# JHP.net
KiCad netlist of a schematic drawn in EasyEDA Pro
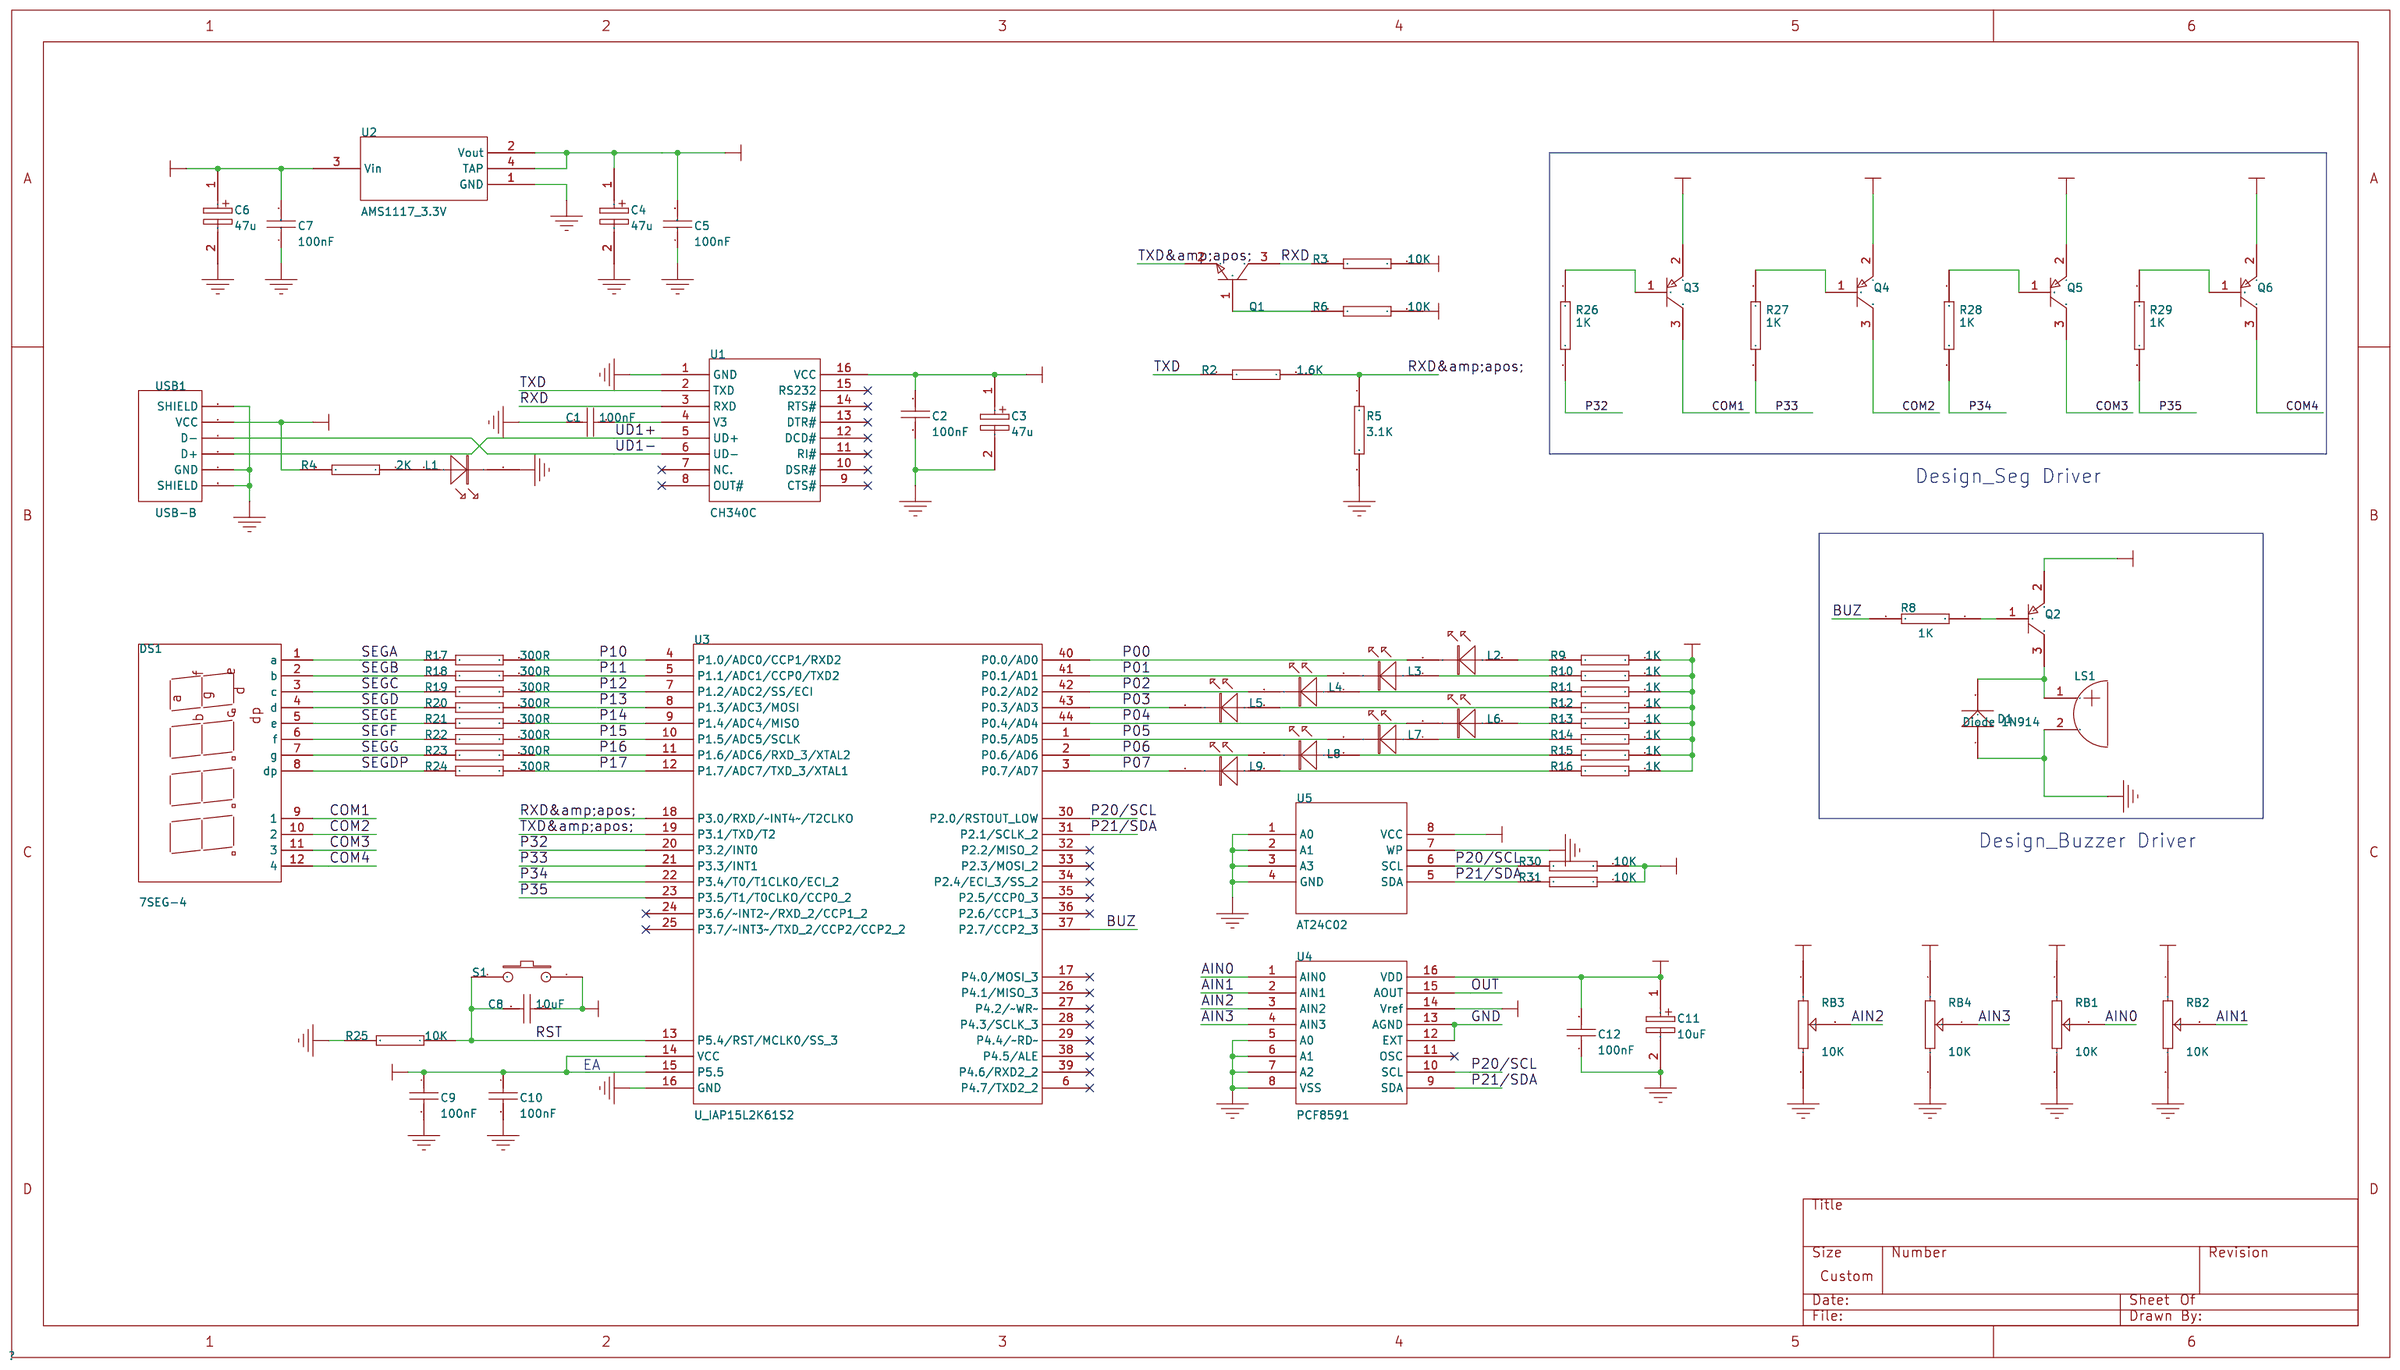
[diagram p0: schematic sheet]

(export (version "E")
  (design (tool "Eeschema 10.0.6"))
  (components
    (comp (ref "C1") (value "100nF") (libsource (lib "easyedapro") (part "CAP")))
    (comp (ref "C2") (value "100nF") (libsource (lib "easyedapro") (part "CAP")))
    (comp (ref "C3")
      (value "47u")
      (description "Electrolytic Capacitor")
      (libsource (lib "easyedapro") (part "CAP-2"))
    )
    (comp (ref "C4")
      (value "47u")
      (description "Electrolytic Capacitor")
      (libsource (lib "easyedapro") (part "CAP-2"))
    )
    (comp (ref "C5") (value "100nF") (description "Capacitor") (libsource (lib "easyedapro") (part "C_CAP")))
    (comp (ref "C6")
      (value "47u")
      (description "Electrolytic Capacitor")
      (libsource (lib "easyedapro") (part "CAP-2"))
    )
    (comp (ref "C7") (value "100nF") (description "Capacitor") (libsource (lib "easyedapro") (part "C_CAP")))
    (comp (ref "C8") (value "10uF") (libsource (lib "easyedapro") (part "CAP")))
    (comp (ref "C9") (value "100nF") (libsource (lib "easyedapro") (part "CAP")))
    (comp (ref "C10") (value "100nF") (libsource (lib "easyedapro") (part "CAP")))
    (comp (ref "C11")
      (value "10uF")
      (description "Electrolytic Capacitor")
      (libsource (lib "easyedapro") (part "ELECTRO2"))
    )
    (comp (ref "C12") (value "100nF") (description "Capacitor") (libsource (lib "easyedapro") (part "CAP")))
    (comp (ref "D1")
      (value "Diode 1N914")
      (description "High Conductance Fast Diode")
      (libsource (lib "easyedapro") (part "Diode 1N914"))
    )
    (comp (ref "DS1")
      (value "7SEG-4")
      (description "4 Seven-Segment Display, Right Hand Decimal")
      (libsource (lib "easyedapro") (part "7SEG-4"))
    )
    (comp (ref "L1") (value "LED") (libsource (lib "easyedapro") (part "LED")))
    (comp (ref "L2") (value "LED") (libsource (lib "easyedapro") (part "LED")))
    (comp (ref "L3") (value "LED") (libsource (lib "easyedapro") (part "LED")))
    (comp (ref "L4") (value "LED") (libsource (lib "easyedapro") (part "LED")))
    (comp (ref "L5") (value "LED") (libsource (lib "easyedapro") (part "LED")))
    (comp (ref "L6") (value "LED") (libsource (lib "easyedapro") (part "LED")))
    (comp (ref "L7") (value "LED") (libsource (lib "easyedapro") (part "LED")))
    (comp (ref "L8") (value "LED") (libsource (lib "easyedapro") (part "LED")))
    (comp (ref "L9") (value "LED") (libsource (lib "easyedapro") (part "LED")))
    (comp (ref "LS1") (value "S_BUZZER") (libsource (lib "easyedapro") (part "S_BUZZER")))
    (comp (ref "Q1")
      (value "8050-SOT23")
      (description "PNP-S8050")
      (libsource (lib "easyedapro") (part "Q_NPN"))
    )
    (comp (ref "Q2")
      (value "2N3906")
      (description "PNP General Purpose Amplifier")
      (libsource (lib "easyedapro") (part "2N3906"))
    )
    (comp (ref "Q3")
      (value "2N3906")
      (description "PNP General Purpose Amplifier")
      (libsource (lib "easyedapro") (part "2N3906"))
    )
    (comp (ref "Q4")
      (value "2N3906")
      (description "PNP General Purpose Amplifier")
      (libsource (lib "easyedapro") (part "2N3906"))
    )
    (comp (ref "Q5")
      (value "2N3906")
      (description "PNP General Purpose Amplifier")
      (libsource (lib "easyedapro") (part "2N3906"))
    )
    (comp (ref "Q6")
      (value "2N3906")
      (description "PNP General Purpose Amplifier")
      (libsource (lib "easyedapro") (part "2N3906"))
    )
    (comp (ref "R2") (value "1.6K") (libsource (lib "easyedapro") (part "RES2")))
    (comp (ref "R3") (value "10K") (libsource (lib "easyedapro") (part "RES2")))
    (comp (ref "R4") (value "2K") (libsource (lib "easyedapro") (part "RES2")))
    (comp (ref "R5") (value "3.1K") (libsource (lib "easyedapro") (part "RES2")))
    (comp (ref "R6") (value "10K") (libsource (lib "easyedapro") (part "RES2")))
    (comp (ref "R8") (value "1K") (libsource (lib "easyedapro") (part "RES2")))
    (comp (ref "R9") (value "1K") (libsource (lib "easyedapro") (part "RES2")))
    (comp (ref "R10") (value "1K") (libsource (lib "easyedapro") (part "RES2")))
    (comp (ref "R11") (value "1K") (libsource (lib "easyedapro") (part "RES2")))
    (comp (ref "R12") (value "1K") (libsource (lib "easyedapro") (part "RES2")))
    (comp (ref "R13") (value "1K") (libsource (lib "easyedapro") (part "RES2")))
    (comp (ref "R14") (value "1K") (libsource (lib "easyedapro") (part "RES2")))
    (comp (ref "R15") (value "1K") (libsource (lib "easyedapro") (part "RES2")))
    (comp (ref "R16") (value "1K") (libsource (lib "easyedapro") (part "RES2")))
    (comp (ref "R17") (value "300R") (libsource (lib "easyedapro") (part "RES2")))
    (comp (ref "R18") (value "300R") (libsource (lib "easyedapro") (part "RES2")))
    (comp (ref "R19") (value "300R") (libsource (lib "easyedapro") (part "RES2")))
    (comp (ref "R20") (value "300R") (libsource (lib "easyedapro") (part "RES2")))
    (comp (ref "R21") (value "300R") (libsource (lib "easyedapro") (part "RES2")))
    (comp (ref "R22") (value "300R") (libsource (lib "easyedapro") (part "RES2")))
    (comp (ref "R23") (value "300R") (libsource (lib "easyedapro") (part "RES2")))
    (comp (ref "R24") (value "300R") (libsource (lib "easyedapro") (part "RES2")))
    (comp (ref "R25") (value "10K") (libsource (lib "easyedapro") (part "RES2")))
    (comp (ref "R26") (value "1K") (libsource (lib "easyedapro") (part "RES2")))
    (comp (ref "R27") (value "1K") (libsource (lib "easyedapro") (part "RES2")))
    (comp (ref "R28") (value "1K") (libsource (lib "easyedapro") (part "RES2")))
    (comp (ref "R29") (value "1K") (libsource (lib "easyedapro") (part "RES2")))
    (comp (ref "R30") (value "10K") (libsource (lib "easyedapro") (part "RES2")))
    (comp (ref "R31") (value "10K") (libsource (lib "easyedapro") (part "RES2")))
    (comp (ref "RB1")
      (value "10K")
      (description "Potentiometer")
      (libsource (lib "easyedapro") (part "POT2"))
    )
    (comp (ref "RB2")
      (value "10K")
      (description "Potentiometer")
      (libsource (lib "easyedapro") (part "POT2"))
    )
    (comp (ref "RB3")
      (value "10K")
      (description "Potentiometer")
      (libsource (lib "easyedapro") (part "POT2"))
    )
    (comp (ref "RB4")
      (value "10K")
      (description "Potentiometer")
      (libsource (lib "easyedapro") (part "POT2"))
    )
    (comp (ref "S1") (value "SW-PB") (libsource (lib "easyedapro") (part "SW-PB")))
    (comp (ref "U1") (value "CH340C") (libsource (lib "easyedapro") (part "CH340C")))
    (comp (ref "U2")
      (value "AMS1117_3.3V")
      (description "POWER")
      (libsource (lib "easyedapro") (part "U_ASM1117"))
    )
    (comp (ref "U3")
      (value "U_IAP15L2K61S2")
      (description "MCU")
      (libsource (lib "easyedapro") (part "U_IAP15F2K61S2"))
    )
    (comp (ref "U4") (value "PCF8591") (libsource (lib "easyedapro") (part "PCF8591")))
    (comp (ref "U5") (value "AT24C02") (libsource (lib "easyedapro") (part "AT24C02")))
    (comp (ref "USB1")
      (value "USB-B")
      (description "Connector")
      (libsource (lib "easyedapro") (part "USB_A"))
    )
  )
  (nets
    (net (code "1") (name "+3V3") (class "Default")
      (node (ref "C10") (pin "1") (pintype "unspecified"))
      (node (ref "C11") (pin "1") (pinfunction "1_1") (pintype "unspecified"))
      (node (ref "C12") (pin "2") (pintype "unspecified"))
      (node (ref "C4") (pin "1") (pinfunction "1_1") (pintype "unspecified"))
      (node (ref "C5") (pin "2") (pinfunction "2_2") (pintype "unspecified"))
      (node (ref "C8") (pin "2") (pintype "unspecified"))
      (node (ref "C9") (pin "1") (pintype "unspecified"))
      (node (ref "Q2") (pin "2") (pinfunction "E_2") (pintype "unspecified"))
      (node (ref "Q3") (pin "2") (pinfunction "E_2") (pintype "unspecified"))
      (node (ref "Q4") (pin "2") (pinfunction "E_2") (pintype "unspecified"))
      (node (ref "Q5") (pin "2") (pinfunction "E_2") (pintype "unspecified"))
      (node (ref "Q6") (pin "2") (pinfunction "E_2") (pintype "unspecified"))
      (node (ref "R10") (pin "2") (pinfunction "2_2") (pintype "unspecified"))
      (node (ref "R11") (pin "2") (pinfunction "2_2") (pintype "unspecified"))
      (node (ref "R12") (pin "2") (pinfunction "2_2") (pintype "unspecified"))
      (node (ref "R13") (pin "2") (pinfunction "2_2") (pintype "unspecified"))
      (node (ref "R14") (pin "2") (pinfunction "2_2") (pintype "unspecified"))
      (node (ref "R15") (pin "2") (pinfunction "2_2") (pintype "unspecified"))
      (node (ref "R16") (pin "2") (pinfunction "2_2") (pintype "unspecified"))
      (node (ref "R30") (pin "1") (pinfunction "1_1") (pintype "unspecified"))
      (node (ref "R31") (pin "1") (pinfunction "1_1") (pintype "unspecified"))
      (node (ref "R6") (pin "1") (pinfunction "1_1") (pintype "unspecified"))
      (node (ref "R9") (pin "2") (pinfunction "2_2") (pintype "unspecified"))
      (node (ref "RB1") (pin "1") (pinfunction "1_1") (pintype "unspecified"))
      (node (ref "RB2") (pin "1") (pinfunction "1_1") (pintype "unspecified"))
      (node (ref "RB3") (pin "1") (pinfunction "1_1") (pintype "unspecified"))
      (node (ref "RB4") (pin "1") (pinfunction "1_1") (pintype "unspecified"))
      (node (ref "S1") (pin "2") (pinfunction "2_2") (pintype "unspecified"))
      (node (ref "U2") (pin "2") (pinfunction "Vout_2") (pintype "unspecified"))
      (node (ref "U2") (pin "4") (pinfunction "TAP_4") (pintype "unspecified"))
      (node (ref "U3") (pin "14") (pinfunction "VCC_14") (pintype "unspecified"))
      (node (ref "U3") (pin "15") (pinfunction "P5.5_15") (pintype "bidirectional"))
      (node (ref "U4") (pin "14") (pinfunction "Vref_14") (pintype "unspecified"))
      (node (ref "U4") (pin "16") (pinfunction "VDD_16") (pintype "unspecified"))
      (node (ref "U5") (pin "8") (pinfunction "VCC_8") (pintype "unspecified"))
    )
    (net (code "2") (name "+5V") (class "Default")
      (node (ref "C2") (pin "1") (pintype "unspecified"))
      (node (ref "C3") (pin "1") (pinfunction "1_1") (pintype "unspecified"))
      (node (ref "C6") (pin "1") (pinfunction "1_1") (pintype "unspecified"))
      (node (ref "C7") (pin "2") (pinfunction "2_2") (pintype "unspecified"))
      (node (ref "R3") (pin "1") (pinfunction "1_1") (pintype "unspecified"))
      (node (ref "R4") (pin "2") (pinfunction "2_2") (pintype "unspecified"))
      (node (ref "U1") (pin "16") (pinfunction "VCC_16") (pintype "unspecified"))
      (node (ref "U2") (pin "3") (pinfunction "Vin_3") (pintype "unspecified"))
      (node (ref "USB1") (pin "1") (pinfunction "VCC_1") (pintype "unspecified"))
    )
    (net (code "3") (name "/AIN0") (class "Default")
      (node (ref "RB1") (pin "2") (pinfunction "W_2") (pintype "unspecified"))
      (node (ref "U4") (pin "1") (pinfunction "AIN0_1") (pintype "unspecified"))
    )
    (net (code "4") (name "/AIN1") (class "Default")
      (node (ref "RB2") (pin "2") (pinfunction "W_2") (pintype "unspecified"))
      (node (ref "U4") (pin "2") (pinfunction "AIN1_2") (pintype "unspecified"))
    )
    (net (code "5") (name "/AIN2") (class "Default")
      (node (ref "RB3") (pin "2") (pinfunction "W_2") (pintype "unspecified"))
      (node (ref "U4") (pin "3") (pinfunction "AIN2_3") (pintype "unspecified"))
    )
    (net (code "6") (name "/AIN3") (class "Default")
      (node (ref "RB4") (pin "2") (pinfunction "W_2") (pintype "unspecified"))
      (node (ref "U4") (pin "4") (pinfunction "AIN3_4") (pintype "unspecified"))
    )
    (net (code "7") (name "/BUZ") (class "Default")
      (node (ref "R8") (pin "1") (pinfunction "1_1") (pintype "unspecified"))
      (node (ref "U3") (pin "37") (pinfunction "P2.7/CCP2_3_37") (pintype "bidirectional"))
    )
    (net (code "8") (name "/COM1") (class "Default")
      (node (ref "DS1") (pin "9") (pinfunction "1_9") (pintype "unspecified"))
      (node (ref "Q3") (pin "3") (pinfunction "C_3") (pintype "unspecified"))
    )
    (net (code "9") (name "/COM2") (class "Default")
      (node (ref "DS1") (pin "10") (pinfunction "2_10") (pintype "unspecified"))
      (node (ref "Q4") (pin "3") (pinfunction "C_3") (pintype "unspecified"))
    )
    (net (code "10") (name "/COM3") (class "Default")
      (node (ref "DS1") (pin "11") (pinfunction "3_11") (pintype "unspecified"))
      (node (ref "Q5") (pin "3") (pinfunction "C_3") (pintype "unspecified"))
    )
    (net (code "11") (name "/COM4") (class "Default")
      (node (ref "DS1") (pin "12") (pinfunction "4_12") (pintype "unspecified"))
      (node (ref "Q6") (pin "3") (pinfunction "C_3") (pintype "unspecified"))
    )
    (net (code "12") (name "/OUT") (class "Default")
      (node (ref "U4") (pin "15") (pinfunction "AOUT_15") (pintype "unspecified"))
    )
    (net (code "13") (name "/P00") (class "Default")
      (node (ref "L2") (pin "2") (pinfunction "K_2") (pintype "unspecified"))
      (node (ref "U3") (pin "40") (pinfunction "P0.0/AD0_40") (pintype "bidirectional"))
    )
    (net (code "14") (name "/P01") (class "Default")
      (node (ref "L3") (pin "2") (pinfunction "K_2") (pintype "unspecified"))
      (node (ref "U3") (pin "41") (pinfunction "P0.1/AD1_41") (pintype "bidirectional"))
    )
    (net (code "15") (name "/P02") (class "Default")
      (node (ref "L4") (pin "2") (pinfunction "K_2") (pintype "unspecified"))
      (node (ref "U3") (pin "42") (pinfunction "P0.2/AD2_42") (pintype "bidirectional"))
    )
    (net (code "16") (name "/P03") (class "Default")
      (node (ref "L5") (pin "2") (pinfunction "K_2") (pintype "unspecified"))
      (node (ref "U3") (pin "43") (pinfunction "P0.3/AD3_43") (pintype "bidirectional"))
    )
    (net (code "17") (name "/P04") (class "Default")
      (node (ref "L6") (pin "2") (pinfunction "K_2") (pintype "unspecified"))
      (node (ref "U3") (pin "44") (pinfunction "P0.4/AD4_44") (pintype "bidirectional"))
    )
    (net (code "18") (name "/P05") (class "Default")
      (node (ref "L7") (pin "2") (pinfunction "K_2") (pintype "unspecified"))
      (node (ref "U3") (pin "1") (pinfunction "P0.5/AD5_1") (pintype "bidirectional"))
    )
    (net (code "19") (name "/P06") (class "Default")
      (node (ref "L8") (pin "2") (pinfunction "K_2") (pintype "unspecified"))
      (node (ref "U3") (pin "2") (pinfunction "P0.6/AD6_2") (pintype "bidirectional"))
    )
    (net (code "20") (name "/P07") (class "Default")
      (node (ref "L9") (pin "2") (pinfunction "K_2") (pintype "unspecified"))
      (node (ref "U3") (pin "3") (pinfunction "P0.7/AD7_3") (pintype "bidirectional"))
    )
    (net (code "21") (name "/P10") (class "Default")
      (node (ref "R17") (pin "2") (pinfunction "2_2") (pintype "unspecified"))
      (node (ref "U3") (pin "4") (pinfunction "P1.0/ADC0/CCP1/RXD2_4") (pintype "unspecified"))
    )
    (net (code "22") (name "/P11") (class "Default")
      (node (ref "R18") (pin "2") (pinfunction "2_2") (pintype "unspecified"))
      (node (ref "U3") (pin "5") (pinfunction "P1.1/ADC1/CCP0/TXD2_5") (pintype "unspecified"))
    )
    (net (code "23") (name "/P12") (class "Default")
      (node (ref "R19") (pin "2") (pinfunction "2_2") (pintype "unspecified"))
      (node (ref "U3") (pin "7") (pinfunction "P1.2/ADC2/SS/ECI_7") (pintype "unspecified"))
    )
    (net (code "24") (name "/P13") (class "Default")
      (node (ref "R20") (pin "2") (pinfunction "2_2") (pintype "unspecified"))
      (node (ref "U3") (pin "8") (pinfunction "P1.3/ADC3/MOSI_8") (pintype "unspecified"))
    )
    (net (code "25") (name "/P14") (class "Default")
      (node (ref "R21") (pin "2") (pinfunction "2_2") (pintype "unspecified"))
      (node (ref "U3") (pin "9") (pinfunction "P1.4/ADC4/MISO_9") (pintype "unspecified"))
    )
    (net (code "26") (name "/P15") (class "Default")
      (node (ref "R22") (pin "2") (pinfunction "2_2") (pintype "unspecified"))
      (node (ref "U3") (pin "10") (pinfunction "P1.5/ADC5/SCLK_10") (pintype "unspecified"))
    )
    (net (code "27") (name "/P16") (class "Default")
      (node (ref "R23") (pin "2") (pinfunction "2_2") (pintype "unspecified"))
      (node (ref "U3") (pin "11") (pinfunction "P1.6/ADC6/RXD_3/XTAL2_11") (pintype "bidirectional"))
    )
    (net (code "28") (name "/P17") (class "Default")
      (node (ref "R24") (pin "2") (pinfunction "2_2") (pintype "unspecified"))
      (node (ref "U3") (pin "12") (pinfunction "P1.7/ADC7/TXD_3/XTAL1_12") (pintype "bidirectional"))
    )
    (net (code "29") (name "/P20{slash}SCL") (class "Default")
      (node (ref "R30") (pin "2") (pinfunction "2_2") (pintype "unspecified"))
      (node (ref "U3") (pin "30") (pinfunction "P2.0/RSTOUT_LOW_30") (pintype "bidirectional"))
      (node (ref "U4") (pin "10") (pinfunction "SCL_10") (pintype "unspecified"))
      (node (ref "U5") (pin "6") (pinfunction "SCL_6") (pintype "unspecified"))
    )
    (net (code "30") (name "/P21{slash}SDA") (class "Default")
      (node (ref "R31") (pin "2") (pinfunction "2_2") (pintype "unspecified"))
      (node (ref "U3") (pin "31") (pinfunction "P2.1/SCLK_2_31") (pintype "bidirectional"))
      (node (ref "U4") (pin "9") (pinfunction "SDA_9") (pintype "unspecified"))
      (node (ref "U5") (pin "5") (pinfunction "SDA_5") (pintype "unspecified"))
    )
    (net (code "31") (name "/P32") (class "Default")
      (node (ref "R26") (pin "1") (pinfunction "1_1") (pintype "unspecified"))
      (node (ref "U3") (pin "20") (pinfunction "P3.2/INT0_20") (pintype "unspecified"))
    )
    (net (code "32") (name "/P33") (class "Default")
      (node (ref "R27") (pin "1") (pinfunction "1_1") (pintype "unspecified"))
      (node (ref "U3") (pin "21") (pinfunction "P3.3/INT1_21") (pintype "unspecified"))
    )
    (net (code "33") (name "/P34") (class "Default")
      (node (ref "R28") (pin "1") (pinfunction "1_1") (pintype "unspecified"))
      (node (ref "U3") (pin "22") (pinfunction "P3.4/T0/T1CLKO/ECI_2_22") (pintype "bidirectional"))
    )
    (net (code "34") (name "/P35") (class "Default")
      (node (ref "R29") (pin "1") (pinfunction "1_1") (pintype "unspecified"))
      (node (ref "U3") (pin "23") (pinfunction "P3.5/T1/T0CLKO/CCP0_2_23") (pintype "unspecified"))
    )
    (net (code "35") (name "/RST") (class "Default")
      (node (ref "C8") (pin "1") (pintype "unspecified"))
      (node (ref "R25") (pin "1") (pinfunction "1_1") (pintype "unspecified"))
      (node (ref "S1") (pin "1") (pinfunction "1_1") (pintype "unspecified"))
      (node (ref "U3") (pin "13") (pinfunction "P5.4/RST/MCLK0/SS_3_13") (pintype "bidirectional"))
    )
    (net (code "36") (name "/RXD") (class "Default")
      (node (ref "Q1") (pin "3") (pinfunction "C_3") (pintype "unspecified"))
      (node (ref "R3") (pin "2") (pinfunction "2_2") (pintype "unspecified"))
      (node (ref "U1") (pin "3") (pinfunction "RXD_3") (pintype "unspecified"))
    )
    (net (code "37") (name "/RXD&amp;apos;") (class "Default")
      (node (ref "R2") (pin "1") (pinfunction "1_1") (pintype "unspecified"))
      (node (ref "R5") (pin "1") (pinfunction "1_1") (pintype "unspecified"))
      (node (ref "U3") (pin "18") (pinfunction "P3.0/RXD/~INT4~/T2CLKO_18") (pintype "unspecified"))
    )
    (net (code "38") (name "/SEGA") (class "Default")
      (node (ref "DS1") (pin "1") (pinfunction "a_1") (pintype "unspecified"))
      (node (ref "R17") (pin "1") (pinfunction "1_1") (pintype "unspecified"))
    )
    (net (code "39") (name "/SEGB") (class "Default")
      (node (ref "DS1") (pin "2") (pinfunction "b_2") (pintype "unspecified"))
      (node (ref "R18") (pin "1") (pinfunction "1_1") (pintype "unspecified"))
    )
    (net (code "40") (name "/SEGC") (class "Default")
      (node (ref "DS1") (pin "3") (pinfunction "c_3") (pintype "unspecified"))
      (node (ref "R19") (pin "1") (pinfunction "1_1") (pintype "unspecified"))
    )
    (net (code "41") (name "/SEGD") (class "Default")
      (node (ref "DS1") (pin "4") (pinfunction "d_4") (pintype "unspecified"))
      (node (ref "R20") (pin "1") (pinfunction "1_1") (pintype "unspecified"))
    )
    (net (code "42") (name "/SEGDP") (class "Default")
      (node (ref "DS1") (pin "8") (pinfunction "dp_8") (pintype "unspecified"))
      (node (ref "R24") (pin "1") (pinfunction "1_1") (pintype "unspecified"))
    )
    (net (code "43") (name "/SEGE") (class "Default")
      (node (ref "DS1") (pin "5") (pinfunction "e_5") (pintype "unspecified"))
      (node (ref "R21") (pin "1") (pinfunction "1_1") (pintype "unspecified"))
    )
    (net (code "44") (name "/SEGF") (class "Default")
      (node (ref "DS1") (pin "6") (pinfunction "f_6") (pintype "unspecified"))
      (node (ref "R22") (pin "1") (pinfunction "1_1") (pintype "unspecified"))
    )
    (net (code "45") (name "/SEGG") (class "Default")
      (node (ref "DS1") (pin "7") (pinfunction "g_7") (pintype "unspecified"))
      (node (ref "R23") (pin "1") (pinfunction "1_1") (pintype "unspecified"))
    )
    (net (code "46") (name "/TXD") (class "Default")
      (node (ref "R2") (pin "2") (pinfunction "2_2") (pintype "unspecified"))
      (node (ref "U1") (pin "2") (pinfunction "TXD_2") (pintype "unspecified"))
    )
    (net (code "47") (name "/TXD&amp;apos;") (class "Default")
      (node (ref "Q1") (pin "2") (pinfunction "E_2") (pintype "unspecified"))
      (node (ref "U3") (pin "19") (pinfunction "P3.1/TXD/T2_19") (pintype "unspecified"))
    )
    (net (code "48") (name "/UD1+") (class "Default")
      (node (ref "U1") (pin "5") (pinfunction "UD+_5") (pintype "unspecified"))
      (node (ref "USB1") (pin "3") (pinfunction "D+_3") (pintype "unspecified"))
    )
    (net (code "49") (name "/UD1-") (class "Default")
      (node (ref "U1") (pin "6") (pinfunction "UD-_6") (pintype "unspecified"))
      (node (ref "USB1") (pin "2") (pinfunction "D-_2") (pintype "unspecified"))
    )
    (net (code "50") (name "GND") (class "Default")
      (node (ref "C1") (pin "1") (pintype "unspecified"))
      (node (ref "C10") (pin "2") (pintype "unspecified"))
      (node (ref "C11") (pin "2") (pinfunction "2_2") (pintype "unspecified"))
      (node (ref "C12") (pin "1") (pintype "unspecified"))
      (node (ref "C2") (pin "2") (pintype "unspecified"))
      (node (ref "C3") (pin "2") (pinfunction "2_2") (pintype "unspecified"))
      (node (ref "C4") (pin "2") (pinfunction "2_2") (pintype "unspecified"))
      (node (ref "C5") (pin "1") (pinfunction "1_1") (pintype "unspecified"))
      (node (ref "C6") (pin "2") (pinfunction "2_2") (pintype "unspecified"))
      (node (ref "C7") (pin "1") (pinfunction "1_1") (pintype "unspecified"))
      (node (ref "C9") (pin "2") (pintype "unspecified"))
      (node (ref "D1") (pin "1") (pinfunction "A_1") (pintype "unspecified"))
      (node (ref "L1") (pin "2") (pinfunction "K_2") (pintype "unspecified"))
      (node (ref "LS1") (pin "2") (pinfunction "2_2") (pintype "unspecified"))
      (node (ref "R25") (pin "2") (pinfunction "2_2") (pintype "unspecified"))
      (node (ref "R5") (pin "2") (pinfunction "2_2") (pintype "unspecified"))
      (node (ref "RB1") (pin "3") (pinfunction "2_3") (pintype "unspecified"))
      (node (ref "RB2") (pin "3") (pinfunction "2_3") (pintype "unspecified"))
      (node (ref "RB3") (pin "3") (pinfunction "2_3") (pintype "unspecified"))
      (node (ref "RB4") (pin "3") (pinfunction "2_3") (pintype "unspecified"))
      (node (ref "U1") (pin "1") (pinfunction "GND_1") (pintype "unspecified"))
      (node (ref "U2") (pin "1") (pinfunction "GND_1") (pintype "unspecified"))
      (node (ref "U3") (pin "16") (pinfunction "GND_16") (pintype "unspecified"))
      (node (ref "U4") (pin "12") (pinfunction "EXT_12") (pintype "unspecified"))
      (node (ref "U4") (pin "13") (pinfunction "AGND_13") (pintype "unspecified"))
      (node (ref "U4") (pin "5") (pinfunction "A0_5") (pintype "unspecified"))
      (node (ref "U4") (pin "6") (pinfunction "A1_6") (pintype "unspecified"))
      (node (ref "U4") (pin "7") (pinfunction "A2_7") (pintype "unspecified"))
      (node (ref "U4") (pin "8") (pinfunction "VSS_8") (pintype "unspecified"))
      (node (ref "U5") (pin "1") (pinfunction "A0_1") (pintype "unspecified"))
      (node (ref "U5") (pin "2") (pinfunction "A1_2") (pintype "unspecified"))
      (node (ref "U5") (pin "3") (pinfunction "A3_3") (pintype "unspecified"))
      (node (ref "U5") (pin "4") (pinfunction "GND_4") (pintype "unspecified"))
      (node (ref "U5") (pin "7") (pinfunction "WP_7") (pintype "unspecified"))
      (node (ref "USB1") (pin "4") (pinfunction "GND_4") (pintype "unspecified"))
      (node (ref "USB1") (pin "5") (pinfunction "SHIELD_5") (pintype "unspecified"))
      (node (ref "USB1") (pin "6") (pinfunction "SHIELD_6") (pintype "unspecified"))
    )
    (net (code "51") (name "Net-(D1-K)") (class "Default")
      (node (ref "D1") (pin "2") (pinfunction "K_2") (pintype "unspecified"))
      (node (ref "LS1") (pin "1") (pinfunction "1_1") (pintype "unspecified"))
      (node (ref "Q2") (pin "3") (pinfunction "C_3") (pintype "unspecified"))
    )
    (net (code "52") (name "Net-(L1-A)") (class "Default")
      (node (ref "L1") (pin "1") (pinfunction "A_1") (pintype "unspecified"))
      (node (ref "R4") (pin "1") (pinfunction "1_1") (pintype "unspecified"))
    )
    (net (code "53") (name "Net-(L2-A)") (class "Default")
      (node (ref "L2") (pin "1") (pinfunction "A_1") (pintype "unspecified"))
      (node (ref "R9") (pin "1") (pinfunction "1_1") (pintype "unspecified"))
    )
    (net (code "54") (name "Net-(L3-A)") (class "Default")
      (node (ref "L3") (pin "1") (pinfunction "A_1") (pintype "unspecified"))
      (node (ref "R10") (pin "1") (pinfunction "1_1") (pintype "unspecified"))
    )
    (net (code "55") (name "Net-(L4-A)") (class "Default")
      (node (ref "L4") (pin "1") (pinfunction "A_1") (pintype "unspecified"))
      (node (ref "R11") (pin "1") (pinfunction "1_1") (pintype "unspecified"))
    )
    (net (code "56") (name "Net-(L5-A)") (class "Default")
      (node (ref "L5") (pin "1") (pinfunction "A_1") (pintype "unspecified"))
      (node (ref "R12") (pin "1") (pinfunction "1_1") (pintype "unspecified"))
    )
    (net (code "57") (name "Net-(L6-A)") (class "Default")
      (node (ref "L6") (pin "1") (pinfunction "A_1") (pintype "unspecified"))
      (node (ref "R13") (pin "1") (pinfunction "1_1") (pintype "unspecified"))
    )
    (net (code "58") (name "Net-(L7-A)") (class "Default")
      (node (ref "L7") (pin "1") (pinfunction "A_1") (pintype "unspecified"))
      (node (ref "R14") (pin "1") (pinfunction "1_1") (pintype "unspecified"))
    )
    (net (code "59") (name "Net-(L8-A)") (class "Default")
      (node (ref "L8") (pin "1") (pinfunction "A_1") (pintype "unspecified"))
      (node (ref "R15") (pin "1") (pinfunction "1_1") (pintype "unspecified"))
    )
    (net (code "60") (name "Net-(L9-A)") (class "Default")
      (node (ref "L9") (pin "1") (pinfunction "A_1") (pintype "unspecified"))
      (node (ref "R16") (pin "1") (pinfunction "1_1") (pintype "unspecified"))
    )
    (net (code "61") (name "Net-(Q1-B)") (class "Default")
      (node (ref "Q1") (pin "1") (pinfunction "B_1") (pintype "unspecified"))
      (node (ref "R6") (pin "2") (pinfunction "2_2") (pintype "unspecified"))
    )
    (net (code "62") (name "Net-(Q2-B)") (class "Default")
      (node (ref "Q2") (pin "1") (pinfunction "B_1") (pintype "unspecified"))
      (node (ref "R8") (pin "2") (pinfunction "2_2") (pintype "unspecified"))
    )
    (net (code "63") (name "Net-(Q3-B)") (class "Default")
      (node (ref "Q3") (pin "1") (pinfunction "B_1") (pintype "unspecified"))
      (node (ref "R26") (pin "2") (pinfunction "2_2") (pintype "unspecified"))
    )
    (net (code "64") (name "Net-(Q4-B)") (class "Default")
      (node (ref "Q4") (pin "1") (pinfunction "B_1") (pintype "unspecified"))
      (node (ref "R27") (pin "2") (pinfunction "2_2") (pintype "unspecified"))
    )
    (net (code "65") (name "Net-(Q5-B)") (class "Default")
      (node (ref "Q5") (pin "1") (pinfunction "B_1") (pintype "unspecified"))
      (node (ref "R28") (pin "2") (pinfunction "2_2") (pintype "unspecified"))
    )
    (net (code "66") (name "Net-(Q6-B)") (class "Default")
      (node (ref "Q6") (pin "1") (pinfunction "B_1") (pintype "unspecified"))
      (node (ref "R29") (pin "2") (pinfunction "2_2") (pintype "unspecified"))
    )
    (net (code "67") (name "Net-(U1-V3)") (class "Default")
      (node (ref "C1") (pin "2") (pintype "unspecified"))
      (node (ref "U1") (pin "4") (pinfunction "V3_4") (pintype "unspecified"))
    )
    (net (code "68") (name "unconnected-(U1-CTS#-Pad9)") (class "Default")
      (node (ref "U1") (pin "9") (pinfunction "CTS#_9") (pintype "unspecified+no_connect"))
    )
    (net (code "69") (name "unconnected-(U1-DCD#-Pad12)") (class "Default")
      (node (ref "U1") (pin "12") (pinfunction "DCD#_12") (pintype "unspecified+no_connect"))
    )
    (net (code "70") (name "unconnected-(U1-DSR#-Pad10)") (class "Default")
      (node (ref "U1") (pin "10") (pinfunction "DSR#_10") (pintype "unspecified+no_connect"))
    )
    (net (code "71") (name "unconnected-(U1-DTR#-Pad13)") (class "Default")
      (node (ref "U1") (pin "13") (pinfunction "DTR#_13") (pintype "unspecified+no_connect"))
    )
    (net (code "72") (name "unconnected-(U1-NC.-Pad7)") (class "Default")
      (node (ref "U1") (pin "7") (pinfunction "NC._7") (pintype "unspecified+no_connect"))
    )
    (net (code "73") (name "unconnected-(U1-OUT#-Pad8)") (class "Default")
      (node (ref "U1") (pin "8") (pinfunction "OUT#_8") (pintype "unspecified+no_connect"))
    )
    (net (code "74") (name "unconnected-(U1-RI#-Pad11)") (class "Default")
      (node (ref "U1") (pin "11") (pinfunction "RI#_11") (pintype "unspecified+no_connect"))
    )
    (net (code "75") (name "unconnected-(U1-RS232-Pad15)") (class "Default")
      (node (ref "U1") (pin "15") (pinfunction "RS232_15") (pintype "unspecified+no_connect"))
    )
    (net (code "76") (name "unconnected-(U1-RTS#-Pad14)") (class "Default")
      (node (ref "U1") (pin "14") (pinfunction "RTS#_14") (pintype "unspecified+no_connect"))
    )
    (net (code "77") (name "unconnected-(U3-P2.2{slash}MISO_2-Pad32)") (class "Default")
      (node (ref "U3") (pin "32") (pinfunction "P2.2/MISO_2_32") (pintype "bidirectional+no_connect"))
    )
    (net (code "78") (name "unconnected-(U3-P2.3{slash}MOSI_2-Pad33)") (class "Default")
      (node (ref "U3") (pin "33") (pinfunction "P2.3/MOSI_2_33") (pintype "bidirectional+no_connect"))
    )
    (net (code "79") (name "unconnected-(U3-P2.4{slash}ECI_3{slash}SS_2-Pad34)") (class "Default")
      (node (ref "U3") (pin "34") (pinfunction "P2.4/ECI_3/SS_2_34") (pintype "bidirectional+no_connect"))
    )
    (net (code "80") (name "unconnected-(U3-P2.5{slash}CCP0_3-Pad35)") (class "Default")
      (node (ref "U3") (pin "35") (pinfunction "P2.5/CCP0_3_35") (pintype "bidirectional+no_connect"))
    )
    (net (code "81") (name "unconnected-(U3-P2.6{slash}CCP1_3-Pad36)") (class "Default")
      (node (ref "U3") (pin "36") (pinfunction "P2.6/CCP1_3_36") (pintype "bidirectional+no_connect"))
    )
    (net (code "82") (name "unconnected-(U3-P3.6{slash}~INT2~{slash}RXD_2{slash}CCP1_2-Pad24)") (class "Default")
      (node (ref "U3") (pin "24") (pinfunction "P3.6/~INT2~/RXD_2/CCP1_2_24") (pintype "unspecified+no_connect"))
    )
    (net (code "83") (name "unconnected-(U3-P3.7{slash}~INT3~{slash}TXD_2{slash}CCP2{slash}CCP2_2-Pad25)") (class "Default")
      (node (ref "U3") (pin "25") (pinfunction "P3.7/~INT3~/TXD_2/CCP2/CCP2_2_25") (pintype "unspecified+no_connect"))
    )
    (net (code "84") (name "unconnected-(U3-P4.0{slash}MOSI_3-Pad17)") (class "Default")
      (node (ref "U3") (pin "17") (pinfunction "P4.0/MOSI_3_17") (pintype "bidirectional+no_connect"))
    )
    (net (code "85") (name "unconnected-(U3-P4.1{slash}MISO_3-Pad26)") (class "Default")
      (node (ref "U3") (pin "26") (pinfunction "P4.1/MISO_3_26") (pintype "bidirectional+no_connect"))
    )
    (net (code "86") (name "unconnected-(U3-P4.2{slash}~WR~-Pad27)") (class "Default")
      (node (ref "U3") (pin "27") (pinfunction "P4.2/~WR~_27") (pintype "unspecified+no_connect"))
    )
    (net (code "87") (name "unconnected-(U3-P4.3{slash}SCLK_3-Pad28)") (class "Default")
      (node (ref "U3") (pin "28") (pinfunction "P4.3/SCLK_3_28") (pintype "bidirectional+no_connect"))
    )
    (net (code "88") (name "unconnected-(U3-P4.4{slash}~RD~-Pad29)") (class "Default")
      (node (ref "U3") (pin "29") (pinfunction "P4.4/~RD~_29") (pintype "unspecified+no_connect"))
    )
    (net (code "89") (name "unconnected-(U3-P4.5{slash}ALE-Pad38)") (class "Default")
      (node (ref "U3") (pin "38") (pinfunction "P4.5/ALE_38") (pintype "unspecified+no_connect"))
    )
    (net (code "90") (name "unconnected-(U3-P4.6{slash}RXD2_2-Pad39)") (class "Default")
      (node (ref "U3") (pin "39") (pinfunction "P4.6/RXD2_2_39") (pintype "unspecified+no_connect"))
    )
    (net (code "91") (name "unconnected-(U3-P4.7{slash}TXD2_2-Pad6)") (class "Default")
      (node (ref "U3") (pin "6") (pinfunction "P4.7/TXD2_2_6") (pintype "bidirectional+no_connect"))
    )
    (net (code "92") (name "unconnected-(U4-OSC-Pad11)") (class "Default")
      (node (ref "U4") (pin "11") (pinfunction "OSC_11") (pintype "unspecified+no_connect"))
    )
  )
)
